# controller.net
KiCad netlist of a schematic drawn in EAGLE
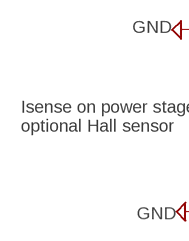
[diagram p0: schematic, sheet 1, part 1 of 2]
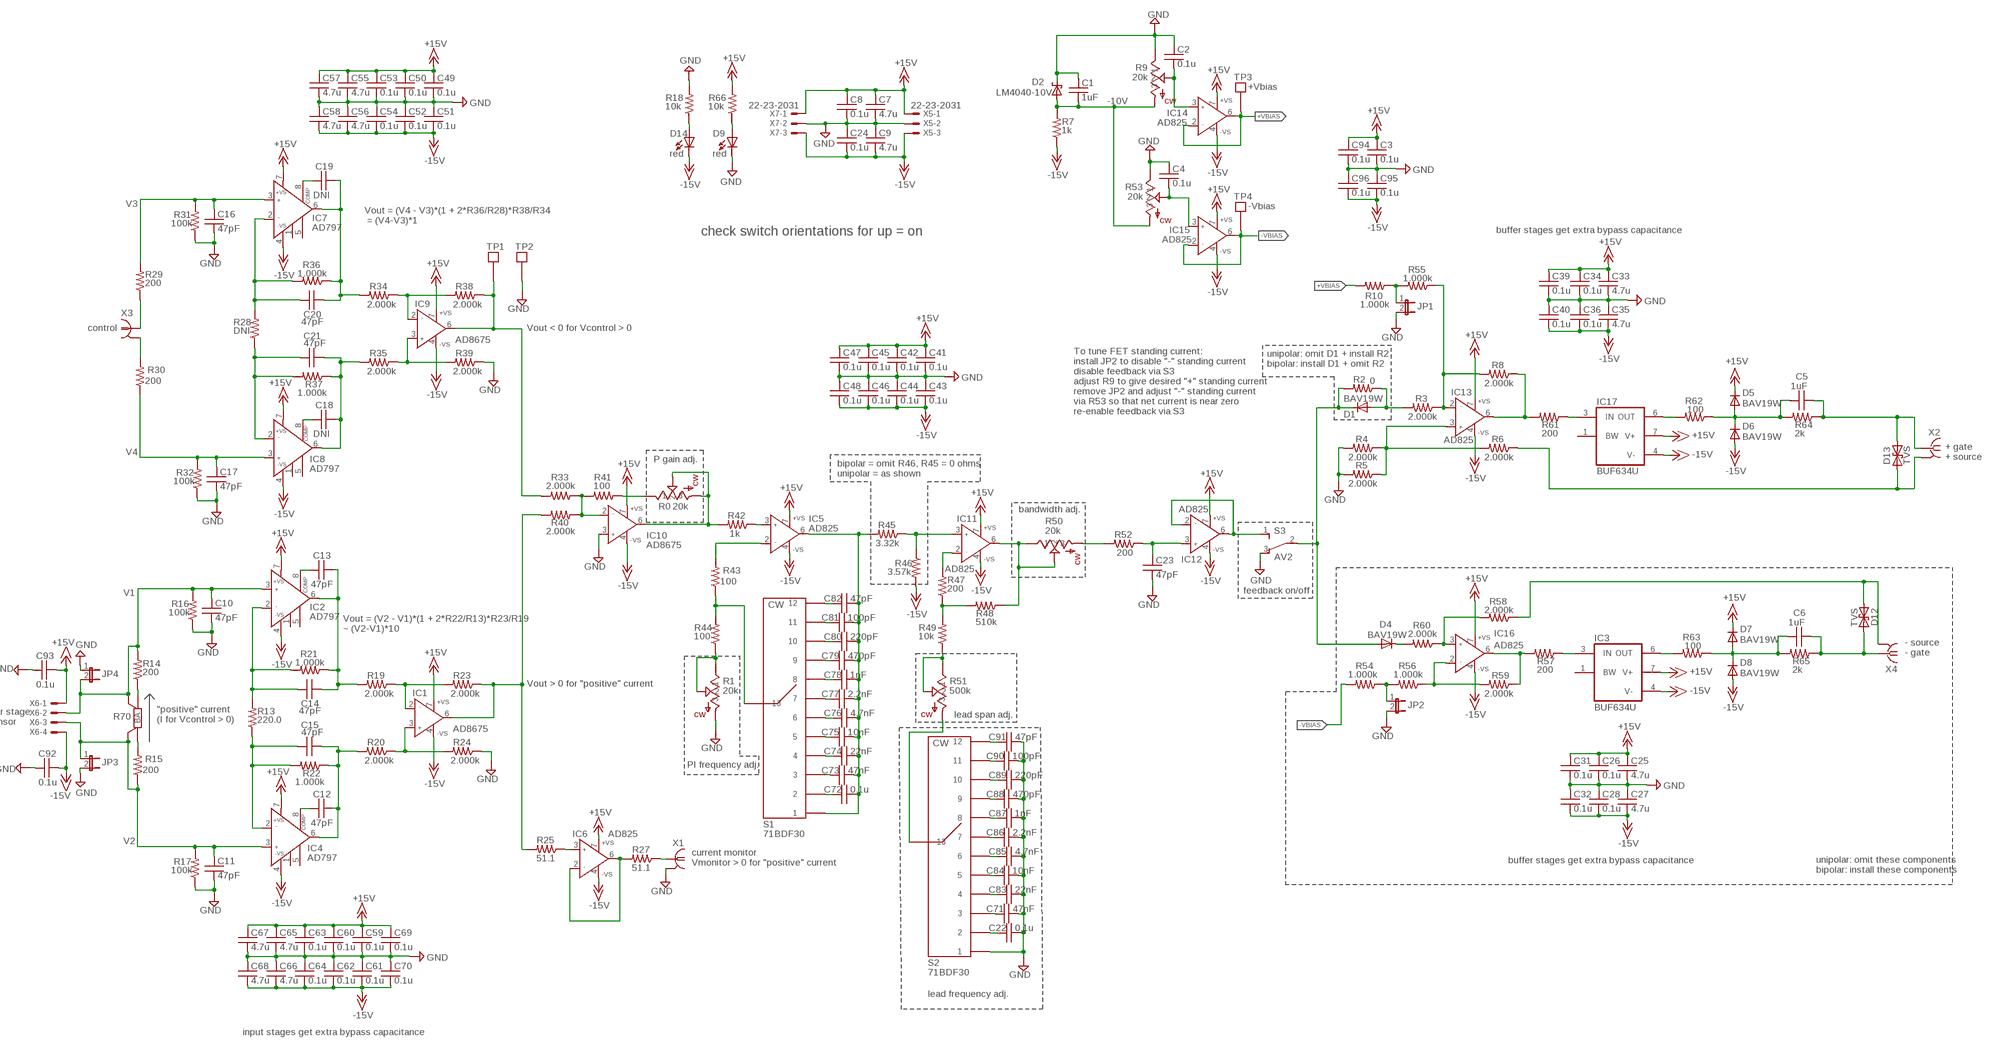
[diagram p1: schematic, sheet 1, part 2 of 2]

(export (version "E")
  (design (tool "Eeschema 10.0.6"))
  (components
    (comp (ref "C1")
      (value "1uF")
      (footprint "eagle-import:0603")
      (libsource (lib "eagle-import") (part "C0603"))
    )
    (comp (ref "C2")
      (value "0.1u")
      (footprint "eagle-import:0603")
      (libsource (lib "eagle-import") (part "C0603"))
    )
    (comp (ref "C3")
      (value "0.1u")
      (footprint "eagle-import:0603")
      (libsource (lib "eagle-import") (part "C0603"))
    )
    (comp (ref "C4")
      (value "0.1u")
      (footprint "eagle-import:0603")
      (libsource (lib "eagle-import") (part "C0603"))
    )
    (comp (ref "C5")
      (value "1uF")
      (footprint "eagle-import:0603")
      (libsource (lib "eagle-import") (part "C0603"))
    )
    (comp (ref "C6")
      (value "1uF")
      (footprint "eagle-import:0603")
      (libsource (lib "eagle-import") (part "C0603"))
    )
    (comp (ref "C7")
      (value "4.7u")
      (footprint "eagle-import:0603")
      (libsource (lib "eagle-import") (part "C0603"))
    )
    (comp (ref "C8")
      (value "0.1u")
      (footprint "eagle-import:0603")
      (libsource (lib "eagle-import") (part "C0603"))
    )
    (comp (ref "C9")
      (value "4.7u")
      (footprint "eagle-import:0603")
      (libsource (lib "eagle-import") (part "C0603"))
    )
    (comp (ref "C10")
      (value "47pF")
      (footprint "eagle-import:0603")
      (libsource (lib "eagle-import") (part "C0603"))
    )
    (comp (ref "C11")
      (value "47pF")
      (footprint "eagle-import:0603")
      (libsource (lib "eagle-import") (part "C0603"))
    )
    (comp (ref "C12")
      (value "47pF")
      (footprint "eagle-import:0603")
      (libsource (lib "eagle-import") (part "C0603"))
    )
    (comp (ref "C13")
      (value "47pF")
      (footprint "eagle-import:0603")
      (libsource (lib "eagle-import") (part "C0603"))
    )
    (comp (ref "C14")
      (value "47pF")
      (footprint "eagle-import:0603")
      (libsource (lib "eagle-import") (part "C0603"))
    )
    (comp (ref "C15")
      (value "47pF")
      (footprint "eagle-import:0603")
      (libsource (lib "eagle-import") (part "C0603"))
    )
    (comp (ref "C16")
      (value "47pF")
      (footprint "eagle-import:0603")
      (libsource (lib "eagle-import") (part "C0603"))
    )
    (comp (ref "C17")
      (value "47pF")
      (footprint "eagle-import:0603")
      (libsource (lib "eagle-import") (part "C0603"))
    )
    (comp (ref "C18")
      (value "DNI")
      (footprint "eagle-import:0603")
      (libsource (lib "eagle-import") (part "C0603"))
    )
    (comp (ref "C19")
      (value "DNI")
      (footprint "eagle-import:0603")
      (libsource (lib "eagle-import") (part "C0603"))
    )
    (comp (ref "C20")
      (value "47pF")
      (footprint "eagle-import:0603")
      (libsource (lib "eagle-import") (part "C0603"))
    )
    (comp (ref "C21")
      (value "47pF")
      (footprint "eagle-import:0603")
      (libsource (lib "eagle-import") (part "C0603"))
    )
    (comp (ref "C22")
      (value "0.1u")
      (footprint "eagle-import:0603")
      (libsource (lib "eagle-import") (part "C0603"))
    )
    (comp (ref "C23")
      (value "47pF")
      (footprint "eagle-import:0603")
      (libsource (lib "eagle-import") (part "C0603"))
    )
    (comp (ref "C24")
      (value "0.1u")
      (footprint "eagle-import:0603")
      (libsource (lib "eagle-import") (part "C0603"))
    )
    (comp (ref "C25")
      (value "4.7u")
      (footprint "eagle-import:0603")
      (libsource (lib "eagle-import") (part "C0603"))
    )
    (comp (ref "C26")
      (value "0.1u")
      (footprint "eagle-import:0603")
      (libsource (lib "eagle-import") (part "C0603"))
    )
    (comp (ref "C27")
      (value "4.7u")
      (footprint "eagle-import:0603")
      (libsource (lib "eagle-import") (part "C0603"))
    )
    (comp (ref "C28")
      (value "0.1u")
      (footprint "eagle-import:0603")
      (libsource (lib "eagle-import") (part "C0603"))
    )
    (comp (ref "C31")
      (value "0.1u")
      (footprint "eagle-import:0603")
      (libsource (lib "eagle-import") (part "C0603"))
    )
    (comp (ref "C32")
      (value "0.1u")
      (footprint "eagle-import:0603")
      (libsource (lib "eagle-import") (part "C0603"))
    )
    (comp (ref "C33")
      (value "4.7u")
      (footprint "eagle-import:0603")
      (libsource (lib "eagle-import") (part "C0603"))
    )
    (comp (ref "C34")
      (value "0.1u")
      (footprint "eagle-import:0603")
      (libsource (lib "eagle-import") (part "C0603"))
    )
    (comp (ref "C35")
      (value "4.7u")
      (footprint "eagle-import:0603")
      (libsource (lib "eagle-import") (part "C0603"))
    )
    (comp (ref "C36")
      (value "0.1u")
      (footprint "eagle-import:0603")
      (libsource (lib "eagle-import") (part "C0603"))
    )
    (comp (ref "C39")
      (value "0.1u")
      (footprint "eagle-import:0603")
      (libsource (lib "eagle-import") (part "C0603"))
    )
    (comp (ref "C40")
      (value "0.1u")
      (footprint "eagle-import:0603")
      (libsource (lib "eagle-import") (part "C0603"))
    )
    (comp (ref "C41")
      (value "0.1u")
      (footprint "eagle-import:0603")
      (libsource (lib "eagle-import") (part "C0603"))
    )
    (comp (ref "C42")
      (value "0.1u")
      (footprint "eagle-import:0603")
      (libsource (lib "eagle-import") (part "C0603"))
    )
    (comp (ref "C43")
      (value "0.1u")
      (footprint "eagle-import:0603")
      (libsource (lib "eagle-import") (part "C0603"))
    )
    (comp (ref "C44")
      (value "0.1u")
      (footprint "eagle-import:0603")
      (libsource (lib "eagle-import") (part "C0603"))
    )
    (comp (ref "C45")
      (value "0.1u")
      (footprint "eagle-import:0603")
      (libsource (lib "eagle-import") (part "C0603"))
    )
    (comp (ref "C46")
      (value "0.1u")
      (footprint "eagle-import:0603")
      (libsource (lib "eagle-import") (part "C0603"))
    )
    (comp (ref "C47")
      (value "0.1u")
      (footprint "eagle-import:0603")
      (libsource (lib "eagle-import") (part "C0603"))
    )
    (comp (ref "C48")
      (value "0.1u")
      (footprint "eagle-import:0603")
      (libsource (lib "eagle-import") (part "C0603"))
    )
    (comp (ref "C49")
      (value "0.1u")
      (footprint "eagle-import:0603")
      (libsource (lib "eagle-import") (part "C0603"))
    )
    (comp (ref "C50")
      (value "0.1u")
      (footprint "eagle-import:0603")
      (libsource (lib "eagle-import") (part "C0603"))
    )
    (comp (ref "C51")
      (value "0.1u")
      (footprint "eagle-import:0603")
      (libsource (lib "eagle-import") (part "C0603"))
    )
    (comp (ref "C52")
      (value "0.1u")
      (footprint "eagle-import:0603")
      (libsource (lib "eagle-import") (part "C0603"))
    )
    (comp (ref "C53")
      (value "0.1u")
      (footprint "eagle-import:0603")
      (libsource (lib "eagle-import") (part "C0603"))
    )
    (comp (ref "C54")
      (value "0.1u")
      (footprint "eagle-import:0603")
      (libsource (lib "eagle-import") (part "C0603"))
    )
    (comp (ref "C55")
      (value "4.7u")
      (footprint "eagle-import:0603")
      (libsource (lib "eagle-import") (part "C0603"))
    )
    (comp (ref "C56")
      (value "4.7u")
      (footprint "eagle-import:0603")
      (libsource (lib "eagle-import") (part "C0603"))
    )
    (comp (ref "C57")
      (value "4.7u")
      (footprint "eagle-import:0603")
      (libsource (lib "eagle-import") (part "C0603"))
    )
    (comp (ref "C58")
      (value "4.7u")
      (footprint "eagle-import:0603")
      (libsource (lib "eagle-import") (part "C0603"))
    )
    (comp (ref "C59")
      (value "0.1u")
      (footprint "eagle-import:0603")
      (libsource (lib "eagle-import") (part "C0603"))
    )
    (comp (ref "C60")
      (value "0.1u")
      (footprint "eagle-import:0603")
      (libsource (lib "eagle-import") (part "C0603"))
    )
    (comp (ref "C61")
      (value "0.1u")
      (footprint "eagle-import:0603")
      (libsource (lib "eagle-import") (part "C0603"))
    )
    (comp (ref "C62")
      (value "0.1u")
      (footprint "eagle-import:0603")
      (libsource (lib "eagle-import") (part "C0603"))
    )
    (comp (ref "C63")
      (value "0.1u")
      (footprint "eagle-import:0603")
      (libsource (lib "eagle-import") (part "C0603"))
    )
    (comp (ref "C64")
      (value "0.1u")
      (footprint "eagle-import:0603")
      (libsource (lib "eagle-import") (part "C0603"))
    )
    (comp (ref "C65")
      (value "4.7u")
      (footprint "eagle-import:0603")
      (libsource (lib "eagle-import") (part "C0603"))
    )
    (comp (ref "C66")
      (value "4.7u")
      (footprint "eagle-import:0603")
      (libsource (lib "eagle-import") (part "C0603"))
    )
    (comp (ref "C67")
      (value "4.7u")
      (footprint "eagle-import:0603")
      (libsource (lib "eagle-import") (part "C0603"))
    )
    (comp (ref "C68")
      (value "4.7u")
      (footprint "eagle-import:0603")
      (libsource (lib "eagle-import") (part "C0603"))
    )
    (comp (ref "C69")
      (value "0.1u")
      (footprint "eagle-import:0603")
      (libsource (lib "eagle-import") (part "C0603"))
    )
    (comp (ref "C70")
      (value "0.1u")
      (footprint "eagle-import:0603")
      (libsource (lib "eagle-import") (part "C0603"))
    )
    (comp (ref "C71")
      (value "47nF")
      (footprint "eagle-import:0603")
      (libsource (lib "eagle-import") (part "C0603"))
    )
    (comp (ref "C72")
      (value "0.1u")
      (footprint "eagle-import:0603")
      (libsource (lib "eagle-import") (part "C0603"))
    )
    (comp (ref "C73")
      (value "47nF")
      (footprint "eagle-import:0603")
      (libsource (lib "eagle-import") (part "C0603"))
    )
    (comp (ref "C74")
      (value "22nF")
      (footprint "eagle-import:0603")
      (libsource (lib "eagle-import") (part "C0603"))
    )
    (comp (ref "C75")
      (value "10nF")
      (footprint "eagle-import:0603")
      (libsource (lib "eagle-import") (part "C0603"))
    )
    (comp (ref "C76")
      (value "4.7nF")
      (footprint "eagle-import:0603")
      (libsource (lib "eagle-import") (part "C0603"))
    )
    (comp (ref "C77")
      (value "2.2nF")
      (footprint "eagle-import:0603")
      (libsource (lib "eagle-import") (part "C0603"))
    )
    (comp (ref "C78")
      (value "1nF")
      (footprint "eagle-import:0603")
      (libsource (lib "eagle-import") (part "C0603"))
    )
    (comp (ref "C79")
      (value "470pF")
      (footprint "eagle-import:0603")
      (libsource (lib "eagle-import") (part "C0603"))
    )
    (comp (ref "C80")
      (value "220pF")
      (footprint "eagle-import:0603")
      (libsource (lib "eagle-import") (part "C0603"))
    )
    (comp (ref "C81")
      (value "100pF")
      (footprint "eagle-import:0603")
      (libsource (lib "eagle-import") (part "C0603"))
    )
    (comp (ref "C82")
      (value "47pF")
      (footprint "eagle-import:0603")
      (libsource (lib "eagle-import") (part "C0603"))
    )
    (comp (ref "C83")
      (value "22nF")
      (footprint "eagle-import:0603")
      (libsource (lib "eagle-import") (part "C0603"))
    )
    (comp (ref "C84")
      (value "10nF")
      (footprint "eagle-import:0603")
      (libsource (lib "eagle-import") (part "C0603"))
    )
    (comp (ref "C85")
      (value "4.7nF")
      (footprint "eagle-import:0603")
      (libsource (lib "eagle-import") (part "C0603"))
    )
    (comp (ref "C86")
      (value "2.2nF")
      (footprint "eagle-import:0603")
      (libsource (lib "eagle-import") (part "C0603"))
    )
    (comp (ref "C87")
      (value "1nF")
      (footprint "eagle-import:0603")
      (libsource (lib "eagle-import") (part "C0603"))
    )
    (comp (ref "C88")
      (value "470pF")
      (footprint "eagle-import:0603")
      (libsource (lib "eagle-import") (part "C0603"))
    )
    (comp (ref "C89")
      (value "220pF")
      (footprint "eagle-import:0603")
      (libsource (lib "eagle-import") (part "C0603"))
    )
    (comp (ref "C90")
      (value "100pF")
      (footprint "eagle-import:0603")
      (libsource (lib "eagle-import") (part "C0603"))
    )
    (comp (ref "C91")
      (value "47pF")
      (footprint "eagle-import:0603")
      (libsource (lib "eagle-import") (part "C0603"))
    )
    (comp (ref "C92")
      (value "0.1u")
      (footprint "eagle-import:0603")
      (libsource (lib "eagle-import") (part "C0603"))
    )
    (comp (ref "C93")
      (value "0.1u")
      (footprint "eagle-import:0603")
      (libsource (lib "eagle-import") (part "C0603"))
    )
    (comp (ref "C94")
      (value "0.1u")
      (footprint "eagle-import:0603")
      (libsource (lib "eagle-import") (part "C0603"))
    )
    (comp (ref "C95")
      (value "0.1u")
      (footprint "eagle-import:0603")
      (libsource (lib "eagle-import") (part "C0603"))
    )
    (comp (ref "C96")
      (value "0.1u")
      (footprint "eagle-import:0603")
      (libsource (lib "eagle-import") (part "C0603"))
    )
    (comp (ref "D1")
      (value "BAV19W")
      (footprint "eagle-import:SOD123")
      (libsource (lib "eagle-import") (part "DIODE-SOD123"))
    )
    (comp (ref "D2")
      (value "LM4040-10V")
      (footprint "eagle-import:SOT23")
      (libsource (lib "eagle-import") (part "LM4040"))
    )
    (comp (ref "D4")
      (value "BAV19W")
      (footprint "eagle-import:SOD123")
      (libsource (lib "eagle-import") (part "DIODE-SOD123"))
    )
    (comp (ref "D5")
      (value "BAV19W")
      (footprint "eagle-import:SOD123")
      (libsource (lib "eagle-import") (part "DIODE-SOD123"))
    )
    (comp (ref "D6")
      (value "BAV19W")
      (footprint "eagle-import:SOD123")
      (libsource (lib "eagle-import") (part "DIODE-SOD123"))
    )
    (comp (ref "D7")
      (value "BAV19W")
      (footprint "eagle-import:SOD123")
      (libsource (lib "eagle-import") (part "DIODE-SOD123"))
    )
    (comp (ref "D8")
      (value "BAV19W")
      (footprint "eagle-import:SOD123")
      (libsource (lib "eagle-import") (part "DIODE-SOD123"))
    )
    (comp (ref "D9")
      (value "red")
      (footprint "eagle-import:LED0603")
      (libsource (lib "eagle-import") (part "LED0603"))
    )
    (comp (ref "D12")
      (value "TVS")
      (footprint "eagle-import:SMA-DIODE")
      (libsource (lib "eagle-import") (part "TVS"))
    )
    (comp (ref "D13")
      (value "TVS")
      (footprint "eagle-import:SMA-DIODE")
      (libsource (lib "eagle-import") (part "TVS"))
    )
    (comp (ref "D14")
      (value "red")
      (footprint "eagle-import:LED0603")
      (libsource (lib "eagle-import") (part "LED0603"))
    )
    (comp (ref "IC1")
      (value "AD8675")
      (footprint "eagle-import:SO8")
      (fields (field (name "MF") "ALTERA CORPORATION") (field (name "MPN") "AD825ARZ"))
      (libsource (lib "eagle-import") (part "AD825_BR"))
    )
    (comp (ref "IC2")
      (value "AD797")
      (footprint "eagle-import:SO8")
      (fields (field (name "MF") "ALTERA CORPORATION") (field (name "MPN") "AD797ARZ"))
      (libsource (lib "eagle-import") (part "AD797_AR"))
    )
    (comp (ref "IC3")
      (value "BUF634U")
      (footprint "eagle-import:SO08")
      (fields (field (name "MF") "TEXAS INSTRUMENTS"))
      (libsource (lib "eagle-import") (part "BUF634U"))
    )
    (comp (ref "IC4")
      (value "AD797")
      (footprint "eagle-import:SO8")
      (fields (field (name "MF") "ALTERA CORPORATION") (field (name "MPN") "AD797ARZ"))
      (libsource (lib "eagle-import") (part "AD797_BR"))
    )
    (comp (ref "IC5")
      (value "AD825")
      (footprint "eagle-import:SO08")
      (libsource (lib "eagle-import") (part "AD825_A"))
    )
    (comp (ref "IC6")
      (value "AD825")
      (footprint "eagle-import:SO08")
      (libsource (lib "eagle-import") (part "AD825_A"))
    )
    (comp (ref "IC7")
      (value "AD797")
      (footprint "eagle-import:SO8")
      (fields (field (name "MF") "ALTERA CORPORATION") (field (name "MPN") "AD797ARZ"))
      (libsource (lib "eagle-import") (part "AD797_AR"))
    )
    (comp (ref "IC8")
      (value "AD797")
      (footprint "eagle-import:SO8")
      (fields (field (name "MF") "ALTERA CORPORATION") (field (name "MPN") "AD797ARZ"))
      (libsource (lib "eagle-import") (part "AD797_BR"))
    )
    (comp (ref "IC9")
      (value "AD8675")
      (footprint "eagle-import:SO8")
      (fields (field (name "MF") "ALTERA CORPORATION") (field (name "MPN") "AD825ARZ"))
      (libsource (lib "eagle-import") (part "AD825_BR"))
    )
    (comp (ref "IC10")
      (value "AD8675")
      (footprint "eagle-import:SO8")
      (fields (field (name "MF") "ALTERA CORPORATION") (field (name "MPN") "AD825ARZ"))
      (libsource (lib "eagle-import") (part "AD825_BR"))
    )
    (comp (ref "IC11")
      (value "AD825")
      (footprint "eagle-import:SO08")
      (libsource (lib "eagle-import") (part "AD825_A"))
    )
    (comp (ref "IC12")
      (value "AD825")
      (footprint "eagle-import:SO8")
      (fields (field (name "MF") "ALTERA CORPORATION") (field (name "MPN") "AD825ARZ"))
      (libsource (lib "eagle-import") (part "AD825_BR"))
    )
    (comp (ref "IC13")
      (value "AD825")
      (footprint "eagle-import:SO8")
      (fields (field (name "MF") "ALTERA CORPORATION") (field (name "MPN") "AD825ARZ"))
      (libsource (lib "eagle-import") (part "AD825_BR"))
    )
    (comp (ref "IC14")
      (value "AD825")
      (footprint "eagle-import:SO08")
      (libsource (lib "eagle-import") (part "AD825_A"))
    )
    (comp (ref "IC15")
      (value "AD825")
      (footprint "eagle-import:SO08")
      (libsource (lib "eagle-import") (part "AD825_A"))
    )
    (comp (ref "IC16")
      (value "AD825")
      (footprint "eagle-import:SO08")
      (libsource (lib "eagle-import") (part "AD825_A"))
    )
    (comp (ref "IC17")
      (value "BUF634U")
      (footprint "eagle-import:SO08")
      (fields (field (name "MF") "TEXAS INSTRUMENTS"))
      (libsource (lib "eagle-import") (part "BUF634U"))
    )
    (comp (ref "JP1")
      (value "JP1E")
      (footprint "eagle-import:JP1")
      (libsource (lib "eagle-import") (part "JP1E"))
    )
    (comp (ref "JP2")
      (value "JP1E")
      (footprint "eagle-import:JP1")
      (libsource (lib "eagle-import") (part "JP1E"))
    )
    (comp (ref "JP3")
      (value "JP1E")
      (footprint "eagle-import:JP1")
      (libsource (lib "eagle-import") (part "JP1E"))
    )
    (comp (ref "JP4")
      (value "JP1E")
      (footprint "eagle-import:JP1")
      (libsource (lib "eagle-import") (part "JP1E"))
    )
    (comp (ref "R0")
      (value "20k")
      (footprint "eagle-import:3590")
      (libsource (lib "eagle-import") (part "POT"))
    )
    (comp (ref "R1")
      (value "20k")
      (footprint "eagle-import:SP19L")
      (libsource (lib "eagle-import") (part "TRIM_US-B90P"))
    )
    (comp (ref "R2")
      (value "0")
      (footprint "eagle-import:0603")
      (libsource (lib "eagle-import") (part "R0603"))
    )
    (comp (ref "R3")
      (value "2.000k")
      (footprint "eagle-import:0603")
      (libsource (lib "eagle-import") (part "R0603"))
    )
    (comp (ref "R4")
      (value "2.000k")
      (footprint "eagle-import:0603")
      (libsource (lib "eagle-import") (part "R0603"))
    )
    (comp (ref "R5")
      (value "2.000k")
      (footprint "eagle-import:0603")
      (libsource (lib "eagle-import") (part "R0603"))
    )
    (comp (ref "R6")
      (value "2.000k")
      (footprint "eagle-import:0603")
      (libsource (lib "eagle-import") (part "R0603"))
    )
    (comp (ref "R7")
      (value "1k")
      (footprint "eagle-import:0603")
      (libsource (lib "eagle-import") (part "R0603"))
    )
    (comp (ref "R8")
      (value "2.000k")
      (footprint "eagle-import:0603")
      (libsource (lib "eagle-import") (part "R0603"))
    )
    (comp (ref "R9")
      (value "20k")
      (footprint "eagle-import:SP19L")
      (libsource (lib "eagle-import") (part "TRIM_US-B90P"))
    )
    (comp (ref "R10")
      (value "1.000k")
      (footprint "eagle-import:0603")
      (libsource (lib "eagle-import") (part "R0603"))
    )
    (comp (ref "R13")
      (value "220.0")
      (footprint "eagle-import:0603")
      (libsource (lib "eagle-import") (part "R0603"))
    )
    (comp (ref "R14")
      (value "200")
      (footprint "eagle-import:0603")
      (libsource (lib "eagle-import") (part "R0603"))
    )
    (comp (ref "R15")
      (value "200")
      (footprint "eagle-import:0603")
      (libsource (lib "eagle-import") (part "R0603"))
    )
    (comp (ref "R16")
      (value "100k")
      (footprint "eagle-import:0603")
      (libsource (lib "eagle-import") (part "R0603"))
    )
    (comp (ref "R17")
      (value "100k")
      (footprint "eagle-import:0603")
      (libsource (lib "eagle-import") (part "R0603"))
    )
    (comp (ref "R18")
      (value "10k")
      (footprint "eagle-import:0603")
      (libsource (lib "eagle-import") (part "R0603"))
    )
    (comp (ref "R19")
      (value "2.000k")
      (footprint "eagle-import:0603")
      (libsource (lib "eagle-import") (part "R0603"))
    )
    (comp (ref "R20")
      (value "2.000k")
      (footprint "eagle-import:0603")
      (libsource (lib "eagle-import") (part "R0603"))
    )
    (comp (ref "R21")
      (value "1.000k")
      (footprint "eagle-import:0603")
      (libsource (lib "eagle-import") (part "R0603"))
    )
    (comp (ref "R22")
      (value "1.000k")
      (footprint "eagle-import:0603")
      (libsource (lib "eagle-import") (part "R0603"))
    )
    (comp (ref "R23")
      (value "2.000k")
      (footprint "eagle-import:0603")
      (libsource (lib "eagle-import") (part "R0603"))
    )
    (comp (ref "R24")
      (value "2.000k")
      (footprint "eagle-import:0603")
      (libsource (lib "eagle-import") (part "R0603"))
    )
    (comp (ref "R25")
      (value "51.1")
      (footprint "eagle-import:0603")
      (libsource (lib "eagle-import") (part "R0603"))
    )
    (comp (ref "R27")
      (value "51.1")
      (footprint "eagle-import:0603")
      (libsource (lib "eagle-import") (part "R0603"))
    )
    (comp (ref "R28")
      (value "DNI")
      (footprint "eagle-import:0603")
      (libsource (lib "eagle-import") (part "R0603"))
    )
    (comp (ref "R29")
      (value "200")
      (footprint "eagle-import:0603")
      (libsource (lib "eagle-import") (part "R0603"))
    )
    (comp (ref "R30")
      (value "200")
      (footprint "eagle-import:0603")
      (libsource (lib "eagle-import") (part "R0603"))
    )
    (comp (ref "R31")
      (value "100k")
      (footprint "eagle-import:0603")
      (libsource (lib "eagle-import") (part "R0603"))
    )
    (comp (ref "R32")
      (value "100k")
      (footprint "eagle-import:0603")
      (libsource (lib "eagle-import") (part "R0603"))
    )
    (comp (ref "R33")
      (value "2.000k")
      (footprint "eagle-import:0603")
      (libsource (lib "eagle-import") (part "R0603"))
    )
    (comp (ref "R34")
      (value "2.000k")
      (footprint "eagle-import:0603")
      (libsource (lib "eagle-import") (part "R0603"))
    )
    (comp (ref "R35")
      (value "2.000k")
      (footprint "eagle-import:0603")
      (libsource (lib "eagle-import") (part "R0603"))
    )
    (comp (ref "R36")
      (value "1.000k")
      (footprint "eagle-import:0603")
      (libsource (lib "eagle-import") (part "R0603"))
    )
    (comp (ref "R37")
      (value "1.000k")
      (footprint "eagle-import:0603")
      (libsource (lib "eagle-import") (part "R0603"))
    )
    (comp (ref "R38")
      (value "2.000k")
      (footprint "eagle-import:0603")
      (libsource (lib "eagle-import") (part "R0603"))
    )
    (comp (ref "R39")
      (value "2.000k")
      (footprint "eagle-import:0603")
      (libsource (lib "eagle-import") (part "R0603"))
    )
    (comp (ref "R40")
      (value "2.000k")
      (footprint "eagle-import:0603")
      (libsource (lib "eagle-import") (part "R0603"))
    )
    (comp (ref "R41")
      (value "100")
      (footprint "eagle-import:0603")
      (libsource (lib "eagle-import") (part "R0603"))
    )
    (comp (ref "R42")
      (value "1k")
      (footprint "eagle-import:0603")
      (libsource (lib "eagle-import") (part "R0603"))
    )
    (comp (ref "R43")
      (value "100")
      (footprint "eagle-import:0603")
      (libsource (lib "eagle-import") (part "R0603"))
    )
    (comp (ref "R44")
      (value "100")
      (footprint "eagle-import:0603")
      (libsource (lib "eagle-import") (part "R0603"))
    )
    (comp (ref "R45")
      (value "3.32k")
      (footprint "eagle-import:0603")
      (libsource (lib "eagle-import") (part "R0603"))
    )
    (comp (ref "R46")
      (value "3.57k")
      (footprint "eagle-import:0603")
      (libsource (lib "eagle-import") (part "R0603"))
    )
    (comp (ref "R47")
      (value "200")
      (footprint "eagle-import:0603")
      (libsource (lib "eagle-import") (part "R0603"))
    )
    (comp (ref "R48")
      (value "510k")
      (footprint "eagle-import:0603")
      (libsource (lib "eagle-import") (part "R0603"))
    )
    (comp (ref "R49")
      (value "10k")
      (footprint "eagle-import:0603")
      (libsource (lib "eagle-import") (part "R0603"))
    )
    (comp (ref "R50")
      (value "20k")
      (footprint "eagle-import:SP19L")
      (libsource (lib "eagle-import") (part "TRIM_US-B90P"))
    )
    (comp (ref "R51")
      (value "500k")
      (footprint "eagle-import:SP19L")
      (libsource (lib "eagle-import") (part "TRIM_US-B90P"))
    )
    (comp (ref "R52")
      (value "200")
      (footprint "eagle-import:0603")
      (libsource (lib "eagle-import") (part "R0603"))
    )
    (comp (ref "R53")
      (value "20k")
      (footprint "eagle-import:SP19L")
      (libsource (lib "eagle-import") (part "TRIM_US-B90P"))
    )
    (comp (ref "R54")
      (value "1.000k")
      (footprint "eagle-import:0603")
      (libsource (lib "eagle-import") (part "R0603"))
    )
    (comp (ref "R55")
      (value "1.000k")
      (footprint "eagle-import:0603")
      (libsource (lib "eagle-import") (part "R0603"))
    )
    (comp (ref "R56")
      (value "1.000k")
      (footprint "eagle-import:0603")
      (libsource (lib "eagle-import") (part "R0603"))
    )
    (comp (ref "R57")
      (value "200")
      (footprint "eagle-import:0603")
      (libsource (lib "eagle-import") (part "R0603"))
    )
    (comp (ref "R58")
      (value "2.000k")
      (footprint "eagle-import:0603")
      (libsource (lib "eagle-import") (part "R0603"))
    )
    (comp (ref "R59")
      (value "2.000k")
      (footprint "eagle-import:0603")
      (libsource (lib "eagle-import") (part "R0603"))
    )
    (comp (ref "R60")
      (value "2.000k")
      (footprint "eagle-import:0603")
      (libsource (lib "eagle-import") (part "R0603"))
    )
    (comp (ref "R61")
      (value "200")
      (footprint "eagle-import:0603")
      (libsource (lib "eagle-import") (part "R0603"))
    )
    (comp (ref "R62")
      (value "100")
      (footprint "eagle-import:0603")
      (libsource (lib "eagle-import") (part "R0603"))
    )
    (comp (ref "R63")
      (value "100")
      (footprint "eagle-import:0603")
      (libsource (lib "eagle-import") (part "R0603"))
    )
    (comp (ref "R64")
      (value "2k")
      (footprint "eagle-import:0603")
      (libsource (lib "eagle-import") (part "R0603"))
    )
    (comp (ref "R65")
      (value "2k")
      (footprint "eagle-import:0603")
      (libsource (lib "eagle-import") (part "R0603"))
    )
    (comp (ref "R66")
      (value "10k")
      (footprint "eagle-import:0603")
      (libsource (lib "eagle-import") (part "R0603"))
    )
    (comp (ref "R70")
      (value "RSENSE")
      (footprint "eagle-import:22-23-2041")
      (libsource (lib "eagle-import") (part "RSENSE"))
    )
    (comp (ref "S1")
      (value "71BDF30")
      (footprint "eagle-import:71BDF")
      (libsource (lib "eagle-import") (part "71BDF30"))
    )
    (comp (ref "S2")
      (value "71BDF30")
      (footprint "eagle-import:71BDF")
      (libsource (lib "eagle-import") (part "71BDF30"))
    )
    (comp (ref "S3")
      (value "AV2")
      (footprint "eagle-import:SPDT-AV2")
      (libsource (lib "eagle-import") (part "SPDT"))
    )
    (comp (ref "TP1")
      (value "TESTPOINT")
      (footprint "eagle-import:TESTPOINT")
      (libsource (lib "eagle-import") (part "TESTPOINT"))
    )
    (comp (ref "TP2")
      (value "TESTPOINT")
      (footprint "eagle-import:TESTPOINT")
      (libsource (lib "eagle-import") (part "TESTPOINT"))
    )
    (comp (ref "TP3")
      (value "TESTPOINT")
      (footprint "eagle-import:TESTPOINT")
      (libsource (lib "eagle-import") (part "TESTPOINT"))
    )
    (comp (ref "TP4")
      (value "TESTPOINT")
      (footprint "eagle-import:TESTPOINT")
      (libsource (lib "eagle-import") (part "TESTPOINT"))
    )
    (comp (ref "X1")
      (value "1-227161-0")
      (footprint "eagle-import:AMP_227161")
      (fields (field (name "MF") "TYCO ELECTRONICS") (field (name "MPN") "1-227161"))
      (libsource (lib "eagle-import") (part "?2271611--0"))
    )
    (comp (ref "X2")
      (value "BU-SMA-H")
      (footprint "eagle-import:BU-SMA-H")
      (libsource (lib "eagle-import") (part "BU-SMA-H"))
    )
    (comp (ref "X3")
      (value "1-227161-0")
      (footprint "eagle-import:AMP_227161")
      (fields (field (name "MF") "TYCO ELECTRONICS") (field (name "MPN") "1-227161"))
      (libsource (lib "eagle-import") (part "?2271611--0"))
    )
    (comp (ref "X4")
      (value "BU-SMA-H")
      (footprint "eagle-import:BU-SMA-H")
      (libsource (lib "eagle-import") (part "BU-SMA-H"))
    )
    (comp (ref "X5")
      (value "22-23-2031")
      (footprint "eagle-import:22-23-2031")
      (fields (field (name "MF") "MOLEX"))
      (libsource (lib "eagle-import") (part "22-23-2031"))
    )
    (comp (ref "X6")
      (value "22-23-2041")
      (footprint "eagle-import:22-23-2041")
      (fields (field (name "MF") "MOLEX"))
      (libsource (lib "eagle-import") (part "22-23-2041"))
    )
    (comp (ref "X7")
      (value "22-23-2031")
      (footprint "eagle-import:22-23-2031")
      (fields (field (name "MF") "MOLEX"))
      (libsource (lib "eagle-import") (part "22-23-2031"))
    )
  )
  (nets
    (net (code "1") (name "+15V") (class "Default")
      (node (ref "C25") (pin "1") (pinfunction "1_1") (pintype "passive"))
      (node (ref "C26") (pin "1") (pinfunction "1_1") (pintype "passive"))
      (node (ref "C3") (pin "1") (pinfunction "1_1") (pintype "passive"))
      (node (ref "C31") (pin "1") (pinfunction "1_1") (pintype "passive"))
      (node (ref "C33") (pin "1") (pinfunction "1_1") (pintype "passive"))
      (node (ref "C34") (pin "1") (pinfunction "1_1") (pintype "passive"))
      (node (ref "C39") (pin "1") (pinfunction "1_1") (pintype "passive"))
      (node (ref "C41") (pin "1") (pinfunction "1_1") (pintype "passive"))
      (node (ref "C42") (pin "1") (pinfunction "1_1") (pintype "passive"))
      (node (ref "C45") (pin "1") (pinfunction "1_1") (pintype "passive"))
      (node (ref "C47") (pin "1") (pinfunction "1_1") (pintype "passive"))
      (node (ref "C49") (pin "1") (pinfunction "1_1") (pintype "passive"))
      (node (ref "C50") (pin "1") (pinfunction "1_1") (pintype "passive"))
      (node (ref "C53") (pin "1") (pinfunction "1_1") (pintype "passive"))
      (node (ref "C55") (pin "1") (pinfunction "1_1") (pintype "passive"))
      (node (ref "C57") (pin "1") (pinfunction "1_1") (pintype "passive"))
      (node (ref "C59") (pin "1") (pinfunction "1_1") (pintype "passive"))
      (node (ref "C60") (pin "1") (pinfunction "1_1") (pintype "passive"))
      (node (ref "C63") (pin "1") (pinfunction "1_1") (pintype "passive"))
      (node (ref "C65") (pin "1") (pinfunction "1_1") (pintype "passive"))
      (node (ref "C67") (pin "1") (pinfunction "1_1") (pintype "passive"))
      (node (ref "C69") (pin "1") (pinfunction "1_1") (pintype "passive"))
      (node (ref "C7") (pin "1") (pinfunction "1_1") (pintype "passive"))
      (node (ref "C8") (pin "1") (pinfunction "1_1") (pintype "passive"))
      (node (ref "C93") (pin "2") (pinfunction "2_2") (pintype "passive"))
      (node (ref "C94") (pin "1") (pinfunction "1_1") (pintype "passive"))
      (node (ref "D5") (pin "C") (pinfunction "C_C") (pintype "passive"))
      (node (ref "D7") (pin "C") (pinfunction "C_C") (pintype "passive"))
      (node (ref "IC1") (pin "7") (pinfunction "+VS_7") (pintype "input"))
      (node (ref "IC10") (pin "7") (pinfunction "+VS_7") (pintype "input"))
      (node (ref "IC11") (pin "7") (pinfunction "+VS_7") (pintype "input"))
      (node (ref "IC12") (pin "7") (pinfunction "+VS_7") (pintype "input"))
      (node (ref "IC13") (pin "7") (pinfunction "+VS_7") (pintype "input"))
      (node (ref "IC14") (pin "7") (pinfunction "+VS_7") (pintype "input"))
      (node (ref "IC15") (pin "7") (pinfunction "+VS_7") (pintype "input"))
      (node (ref "IC16") (pin "7") (pinfunction "+VS_7") (pintype "input"))
      (node (ref "IC17") (pin "7") (pinfunction "V+_7") (pintype "power_in"))
      (node (ref "IC2") (pin "7") (pinfunction "+VS_7") (pintype "input"))
      (node (ref "IC3") (pin "7") (pinfunction "V+_7") (pintype "power_in"))
      (node (ref "IC4") (pin "7") (pinfunction "+VS_7") (pintype "input"))
      (node (ref "IC5") (pin "7") (pinfunction "+VS_7") (pintype "input"))
      (node (ref "IC6") (pin "7") (pinfunction "+VS_7") (pintype "input"))
      (node (ref "IC7") (pin "7") (pinfunction "+VS_7") (pintype "input"))
      (node (ref "IC8") (pin "7") (pinfunction "+VS_7") (pintype "input"))
      (node (ref "IC9") (pin "7") (pinfunction "+VS_7") (pintype "input"))
      (node (ref "R66") (pin "2") (pinfunction "2_2") (pintype "passive"))
      (node (ref "X5") (pin "1") (pinfunction "S_1") (pintype "passive"))
      (node (ref "X6") (pin "1") (pinfunction "S_1") (pintype "passive"))
      (node (ref "X7") (pin "1") (pinfunction "S_1") (pintype "passive"))
    )
    (net (code "2") (name "+VBIAS") (class "Default")
      (node (ref "IC14") (pin "2") (pinfunction "IN-_2") (pintype "input"))
      (node (ref "IC14") (pin "6") (pinfunction "OUT_6") (pintype "output"))
      (node (ref "R10") (pin "2") (pinfunction "2_2") (pintype "passive"))
      (node (ref "TP3") (pin "P$1") (pinfunction "P$1_P$1") (pintype "bidirectional"))
    )
    (net (code "3") (name "-15V") (class "Default")
      (node (ref "C24") (pin "2") (pinfunction "2_2") (pintype "passive"))
      (node (ref "C27") (pin "2") (pinfunction "2_2") (pintype "passive"))
      (node (ref "C28") (pin "2") (pinfunction "2_2") (pintype "passive"))
      (node (ref "C32") (pin "2") (pinfunction "2_2") (pintype "passive"))
      (node (ref "C35") (pin "2") (pinfunction "2_2") (pintype "passive"))
      (node (ref "C36") (pin "2") (pinfunction "2_2") (pintype "passive"))
      (node (ref "C40") (pin "2") (pinfunction "2_2") (pintype "passive"))
      (node (ref "C43") (pin "2") (pinfunction "2_2") (pintype "passive"))
      (node (ref "C44") (pin "2") (pinfunction "2_2") (pintype "passive"))
      (node (ref "C46") (pin "2") (pinfunction "2_2") (pintype "passive"))
      (node (ref "C48") (pin "2") (pinfunction "2_2") (pintype "passive"))
      (node (ref "C51") (pin "2") (pinfunction "2_2") (pintype "passive"))
      (node (ref "C52") (pin "2") (pinfunction "2_2") (pintype "passive"))
      (node (ref "C54") (pin "2") (pinfunction "2_2") (pintype "passive"))
      (node (ref "C56") (pin "2") (pinfunction "2_2") (pintype "passive"))
      (node (ref "C58") (pin "2") (pinfunction "2_2") (pintype "passive"))
      (node (ref "C61") (pin "2") (pinfunction "2_2") (pintype "passive"))
      (node (ref "C62") (pin "2") (pinfunction "2_2") (pintype "passive"))
      (node (ref "C64") (pin "2") (pinfunction "2_2") (pintype "passive"))
      (node (ref "C66") (pin "2") (pinfunction "2_2") (pintype "passive"))
      (node (ref "C68") (pin "2") (pinfunction "2_2") (pintype "passive"))
      (node (ref "C70") (pin "2") (pinfunction "2_2") (pintype "passive"))
      (node (ref "C9") (pin "2") (pinfunction "2_2") (pintype "passive"))
      (node (ref "C92") (pin "2") (pinfunction "2_2") (pintype "passive"))
      (node (ref "C95") (pin "2") (pinfunction "2_2") (pintype "passive"))
      (node (ref "C96") (pin "2") (pinfunction "2_2") (pintype "passive"))
      (node (ref "D14") (pin "C") (pinfunction "C_C") (pintype "passive"))
      (node (ref "D6") (pin "A") (pinfunction "A_A") (pintype "passive"))
      (node (ref "D8") (pin "A") (pinfunction "A_A") (pintype "passive"))
      (node (ref "IC1") (pin "4") (pinfunction "-VS_4") (pintype "input"))
      (node (ref "IC10") (pin "4") (pinfunction "-VS_4") (pintype "input"))
      (node (ref "IC11") (pin "4") (pinfunction "-VS_4") (pintype "input"))
      (node (ref "IC12") (pin "4") (pinfunction "-VS_4") (pintype "input"))
      (node (ref "IC13") (pin "4") (pinfunction "-VS_4") (pintype "input"))
      (node (ref "IC14") (pin "4") (pinfunction "-VS_4") (pintype "input"))
      (node (ref "IC15") (pin "4") (pinfunction "-VS_4") (pintype "input"))
      (node (ref "IC16") (pin "4") (pinfunction "-VS_4") (pintype "input"))
      (node (ref "IC17") (pin "4") (pinfunction "V-_4") (pintype "power_in"))
      (node (ref "IC2") (pin "4") (pinfunction "-VS_4") (pintype "input"))
      (node (ref "IC3") (pin "4") (pinfunction "V-_4") (pintype "power_in"))
      (node (ref "IC4") (pin "4") (pinfunction "-VS_4") (pintype "input"))
      (node (ref "IC5") (pin "4") (pinfunction "-VS_4") (pintype "input"))
      (node (ref "IC6") (pin "4") (pinfunction "-VS_4") (pintype "input"))
      (node (ref "IC7") (pin "4") (pinfunction "-VS_4") (pintype "input"))
      (node (ref "IC8") (pin "4") (pinfunction "-VS_4") (pintype "input"))
      (node (ref "IC9") (pin "4") (pinfunction "-VS_4") (pintype "input"))
      (node (ref "R46") (pin "2") (pinfunction "2_2") (pintype "passive"))
      (node (ref "R7") (pin "1") (pinfunction "1_1") (pintype "passive"))
      (node (ref "X5") (pin "3") (pinfunction "S_3") (pintype "passive"))
      (node (ref "X6") (pin "4") (pinfunction "S_4") (pintype "passive"))
      (node (ref "X7") (pin "3") (pinfunction "S_3") (pintype "passive"))
    )
    (net (code "4") (name "-VBIAS") (class "Default")
      (node (ref "IC15") (pin "2") (pinfunction "IN-_2") (pintype "input"))
      (node (ref "IC15") (pin "6") (pinfunction "OUT_6") (pintype "output"))
      (node (ref "R54") (pin "2") (pinfunction "2_2") (pintype "passive"))
      (node (ref "TP4") (pin "P$1") (pinfunction "P$1_P$1") (pintype "bidirectional"))
    )
    (net (code "5") (name "GND") (class "Default")
      (node (ref "C1") (pin "1") (pinfunction "1_1") (pintype "passive"))
      (node (ref "C10") (pin "2") (pinfunction "2_2") (pintype "passive"))
      (node (ref "C11") (pin "2") (pinfunction "2_2") (pintype "passive"))
      (node (ref "C16") (pin "2") (pinfunction "2_2") (pintype "passive"))
      (node (ref "C17") (pin "2") (pinfunction "2_2") (pintype "passive"))
      (node (ref "C2") (pin "1") (pinfunction "1_1") (pintype "passive"))
      (node (ref "C22") (pin "2") (pinfunction "2_2") (pintype "passive"))
      (node (ref "C23") (pin "2") (pinfunction "2_2") (pintype "passive"))
      (node (ref "C24") (pin "1") (pinfunction "1_1") (pintype "passive"))
      (node (ref "C25") (pin "2") (pinfunction "2_2") (pintype "passive"))
      (node (ref "C26") (pin "2") (pinfunction "2_2") (pintype "passive"))
      (node (ref "C27") (pin "1") (pinfunction "1_1") (pintype "passive"))
      (node (ref "C28") (pin "1") (pinfunction "1_1") (pintype "passive"))
      (node (ref "C3") (pin "2") (pinfunction "2_2") (pintype "passive"))
      (node (ref "C31") (pin "2") (pinfunction "2_2") (pintype "passive"))
      (node (ref "C32") (pin "1") (pinfunction "1_1") (pintype "passive"))
      (node (ref "C33") (pin "2") (pinfunction "2_2") (pintype "passive"))
      (node (ref "C34") (pin "2") (pinfunction "2_2") (pintype "passive"))
      (node (ref "C35") (pin "1") (pinfunction "1_1") (pintype "passive"))
      (node (ref "C36") (pin "1") (pinfunction "1_1") (pintype "passive"))
      (node (ref "C39") (pin "2") (pinfunction "2_2") (pintype "passive"))
      (node (ref "C4") (pin "1") (pinfunction "1_1") (pintype "passive"))
      (node (ref "C40") (pin "1") (pinfunction "1_1") (pintype "passive"))
      (node (ref "C41") (pin "2") (pinfunction "2_2") (pintype "passive"))
      (node (ref "C42") (pin "2") (pinfunction "2_2") (pintype "passive"))
      (node (ref "C43") (pin "1") (pinfunction "1_1") (pintype "passive"))
      (node (ref "C44") (pin "1") (pinfunction "1_1") (pintype "passive"))
      (node (ref "C45") (pin "2") (pinfunction "2_2") (pintype "passive"))
      (node (ref "C46") (pin "1") (pinfunction "1_1") (pintype "passive"))
      (node (ref "C47") (pin "2") (pinfunction "2_2") (pintype "passive"))
      (node (ref "C48") (pin "1") (pinfunction "1_1") (pintype "passive"))
      (node (ref "C49") (pin "2") (pinfunction "2_2") (pintype "passive"))
      (node (ref "C50") (pin "2") (pinfunction "2_2") (pintype "passive"))
      (node (ref "C51") (pin "1") (pinfunction "1_1") (pintype "passive"))
      (node (ref "C52") (pin "1") (pinfunction "1_1") (pintype "passive"))
      (node (ref "C53") (pin "2") (pinfunction "2_2") (pintype "passive"))
      (node (ref "C54") (pin "1") (pinfunction "1_1") (pintype "passive"))
      (node (ref "C55") (pin "2") (pinfunction "2_2") (pintype "passive"))
      (node (ref "C56") (pin "1") (pinfunction "1_1") (pintype "passive"))
      (node (ref "C57") (pin "2") (pinfunction "2_2") (pintype "passive"))
      (node (ref "C58") (pin "1") (pinfunction "1_1") (pintype "passive"))
      (node (ref "C59") (pin "2") (pinfunction "2_2") (pintype "passive"))
      (node (ref "C60") (pin "2") (pinfunction "2_2") (pintype "passive"))
      (node (ref "C61") (pin "1") (pinfunction "1_1") (pintype "passive"))
      (node (ref "C62") (pin "1") (pinfunction "1_1") (pintype "passive"))
      (node (ref "C63") (pin "2") (pinfunction "2_2") (pintype "passive"))
      (node (ref "C64") (pin "1") (pinfunction "1_1") (pintype "passive"))
      (node (ref "C65") (pin "2") (pinfunction "2_2") (pintype "passive"))
      (node (ref "C66") (pin "1") (pinfunction "1_1") (pintype "passive"))
      (node (ref "C67") (pin "2") (pinfunction "2_2") (pintype "passive"))
      (node (ref "C68") (pin "1") (pinfunction "1_1") (pintype "passive"))
      (node (ref "C69") (pin "2") (pinfunction "2_2") (pintype "passive"))
      (node (ref "C7") (pin "2") (pinfunction "2_2") (pintype "passive"))
      (node (ref "C70") (pin "1") (pinfunction "1_1") (pintype "passive"))
      (node (ref "C71") (pin "2") (pinfunction "2_2") (pintype "passive"))
      (node (ref "C8") (pin "2") (pinfunction "2_2") (pintype "passive"))
      (node (ref "C83") (pin "2") (pinfunction "2_2") (pintype "passive"))
      (node (ref "C84") (pin "2") (pinfunction "2_2") (pintype "passive"))
      (node (ref "C85") (pin "2") (pinfunction "2_2") (pintype "passive"))
      (node (ref "C86") (pin "2") (pinfunction "2_2") (pintype "passive"))
      (node (ref "C87") (pin "2") (pinfunction "2_2") (pintype "passive"))
      (node (ref "C88") (pin "2") (pinfunction "2_2") (pintype "passive"))
      (node (ref "C89") (pin "2") (pinfunction "2_2") (pintype "passive"))
      (node (ref "C9") (pin "1") (pinfunction "1_1") (pintype "passive"))
      (node (ref "C90") (pin "2") (pinfunction "2_2") (pintype "passive"))
      (node (ref "C91") (pin "2") (pinfunction "2_2") (pintype "passive"))
      (node (ref "C92") (pin "1") (pinfunction "1_1") (pintype "passive"))
      (node (ref "C93") (pin "1") (pinfunction "1_1") (pintype "passive"))
      (node (ref "C94") (pin "2") (pinfunction "2_2") (pintype "passive"))
      (node (ref "C95") (pin "1") (pinfunction "1_1") (pintype "passive"))
      (node (ref "C96") (pin "1") (pinfunction "1_1") (pintype "passive"))
      (node (ref "D2") (pin "1") (pinfunction "C_1") (pintype "passive"))
      (node (ref "D9") (pin "C") (pinfunction "C_C") (pintype "passive"))
      (node (ref "IC10") (pin "3") (pinfunction "IN+_3") (pintype "input"))
      (node (ref "JP1") (pin "2") (pinfunction "2_2") (pintype "passive"))
      (node (ref "JP2") (pin "2") (pinfunction "2_2") (pintype "passive"))
      (node (ref "JP3") (pin "2") (pinfunction "2_2") (pintype "passive"))
      (node (ref "JP4") (pin "1") (pinfunction "1_1") (pintype "passive"))
      (node (ref "R1") (pin "E") (pinfunction "3_E") (pintype "passive"))
      (node (ref "R16") (pin "1") (pinfunction "1_1") (pintype "passive"))
      (node (ref "R17") (pin "1") (pinfunction "1_1") (pintype "passive"))
      (node (ref "R18") (pin "2") (pinfunction "2_2") (pintype "passive"))
      (node (ref "R24") (pin "1") (pinfunction "1_1") (pintype "passive"))
      (node (ref "R31") (pin "1") (pinfunction "1_1") (pintype "passive"))
      (node (ref "R32") (pin "1") (pinfunction "1_1") (pintype "passive"))
      (node (ref "R39") (pin "1") (pinfunction "1_1") (pintype "passive"))
      (node (ref "R4") (pin "2") (pinfunction "2_2") (pintype "passive"))
      (node (ref "R5") (pin "2") (pinfunction "2_2") (pintype "passive"))
      (node (ref "R53") (pin "A") (pinfunction "1_A") (pintype "passive"))
      (node (ref "R9") (pin "A") (pinfunction "1_A") (pintype "passive"))
      (node (ref "S2") (pin "1") (pinfunction "1_1") (pintype "bidirectional"))
      (node (ref "S3") (pin "3") (pinfunction "3_3") (pintype "passive"))
      (node (ref "TP2") (pin "P$1") (pinfunction "P$1_P$1") (pintype "bidirectional"))
      (node (ref "X1") (pin "2") (pinfunction "2_2") (pintype "passive"))
      (node (ref "X5") (pin "2") (pinfunction "S_2") (pintype "passive"))
      (node (ref "X7") (pin "2") (pinfunction "S_2") (pintype "passive"))
    )
    (net (code "6") (name "Net-(C5-Pad1)") (class "Default")
      (node (ref "C5") (pin "1") (pinfunction "1_1") (pintype "passive"))
      (node (ref "D5") (pin "A") (pinfunction "A_A") (pintype "passive"))
      (node (ref "D6") (pin "C") (pinfunction "C_C") (pintype "passive"))
      (node (ref "R62") (pin "1") (pinfunction "1_1") (pintype "passive"))
      (node (ref "R64") (pin "2") (pinfunction "2_2") (pintype "passive"))
    )
    (net (code "7") (name "Net-(C6-Pad1)") (class "Default")
      (node (ref "C6") (pin "1") (pinfunction "1_1") (pintype "passive"))
      (node (ref "D7") (pin "A") (pinfunction "A_A") (pintype "passive"))
      (node (ref "D8") (pin "C") (pinfunction "C_C") (pintype "passive"))
      (node (ref "R63") (pin "1") (pinfunction "1_1") (pintype "passive"))
      (node (ref "R65") (pin "2") (pinfunction "2_2") (pintype "passive"))
    )
    (net (code "8") (name "Net-(C22-Pad1)") (class "Default")
      (node (ref "C22") (pin "1") (pinfunction "1_1") (pintype "passive"))
      (node (ref "S2") (pin "2") (pinfunction "2_2") (pintype "bidirectional"))
    )
    (net (code "9") (name "Net-(C71-Pad1)") (class "Default")
      (node (ref "C71") (pin "1") (pinfunction "1_1") (pintype "passive"))
      (node (ref "S2") (pin "3") (pinfunction "3_3") (pintype "bidirectional"))
    )
    (net (code "10") (name "Net-(C72-Pad1)") (class "Default")
      (node (ref "C72") (pin "1") (pinfunction "1_1") (pintype "passive"))
      (node (ref "S1") (pin "2") (pinfunction "2_2") (pintype "bidirectional"))
    )
    (net (code "11") (name "Net-(C73-Pad1)") (class "Default")
      (node (ref "C73") (pin "1") (pinfunction "1_1") (pintype "passive"))
      (node (ref "S1") (pin "3") (pinfunction "3_3") (pintype "bidirectional"))
    )
    (net (code "12") (name "Net-(C74-Pad1)") (class "Default")
      (node (ref "C74") (pin "1") (pinfunction "1_1") (pintype "passive"))
      (node (ref "S1") (pin "4") (pinfunction "4_4") (pintype "bidirectional"))
    )
    (net (code "13") (name "Net-(C75-Pad1)") (class "Default")
      (node (ref "C75") (pin "1") (pinfunction "1_1") (pintype "passive"))
      (node (ref "S1") (pin "5") (pinfunction "5_5") (pintype "bidirectional"))
    )
    (net (code "14") (name "Net-(C76-Pad1)") (class "Default")
      (node (ref "C76") (pin "1") (pinfunction "1_1") (pintype "passive"))
      (node (ref "S1") (pin "6") (pinfunction "6_6") (pintype "bidirectional"))
    )
    (net (code "15") (name "Net-(C77-Pad1)") (class "Default")
      (node (ref "C77") (pin "1") (pinfunction "1_1") (pintype "passive"))
      (node (ref "S1") (pin "7") (pinfunction "7_7") (pintype "bidirectional"))
    )
    (net (code "16") (name "Net-(C78-Pad1)") (class "Default")
      (node (ref "C78") (pin "1") (pinfunction "1_1") (pintype "passive"))
      (node (ref "S1") (pin "8") (pinfunction "8_8") (pintype "bidirectional"))
    )
    (net (code "17") (name "Net-(C79-Pad1)") (class "Default")
      (node (ref "C79") (pin "1") (pinfunction "1_1") (pintype "passive"))
      (node (ref "S1") (pin "9") (pinfunction "9_9") (pintype "bidirectional"))
    )
    (net (code "18") (name "Net-(C80-Pad1)") (class "Default")
      (node (ref "C80") (pin "1") (pinfunction "1_1") (pintype "passive"))
      (node (ref "S1") (pin "10") (pinfunction "10_10") (pintype "bidirectional"))
    )
    (net (code "19") (name "Net-(C81-Pad1)") (class "Default")
      (node (ref "C81") (pin "1") (pinfunction "1_1") (pintype "passive"))
      (node (ref "S1") (pin "11") (pinfunction "11_11") (pintype "bidirectional"))
    )
    (net (code "20") (name "Net-(C82-Pad1)") (class "Default")
      (node (ref "C82") (pin "1") (pinfunction "1_1") (pintype "passive"))
      (node (ref "S1") (pin "12") (pinfunction "12_12") (pintype "bidirectional"))
    )
    (net (code "21") (name "Net-(C83-Pad1)") (class "Default")
      (node (ref "C83") (pin "1") (pinfunction "1_1") (pintype "passive"))
      (node (ref "S2") (pin "4") (pinfunction "4_4") (pintype "bidirectional"))
    )
    (net (code "22") (name "Net-(C84-Pad1)") (class "Default")
      (node (ref "C84") (pin "1") (pinfunction "1_1") (pintype "passive"))
      (node (ref "S2") (pin "5") (pinfunction "5_5") (pintype "bidirectional"))
    )
    (net (code "23") (name "Net-(C85-Pad1)") (class "Default")
      (node (ref "C85") (pin "1") (pinfunction "1_1") (pintype "passive"))
      (node (ref "S2") (pin "6") (pinfunction "6_6") (pintype "bidirectional"))
    )
    (net (code "24") (name "Net-(C86-Pad1)") (class "Default")
      (node (ref "C86") (pin "1") (pinfunction "1_1") (pintype "passive"))
      (node (ref "S2") (pin "7") (pinfunction "7_7") (pintype "bidirectional"))
    )
    (net (code "25") (name "Net-(C87-Pad1)") (class "Default")
      (node (ref "C87") (pin "1") (pinfunction "1_1") (pintype "passive"))
      (node (ref "S2") (pin "8") (pinfunction "8_8") (pintype "bidirectional"))
    )
    (net (code "26") (name "Net-(C88-Pad1)") (class "Default")
      (node (ref "C88") (pin "1") (pinfunction "1_1") (pintype "passive"))
      (node (ref "S2") (pin "9") (pinfunction "9_9") (pintype "bidirectional"))
    )
    (net (code "27") (name "Net-(C89-Pad1)") (class "Default")
      (node (ref "C89") (pin "1") (pinfunction "1_1") (pintype "passive"))
      (node (ref "S2") (pin "10") (pinfunction "10_10") (pintype "bidirectional"))
    )
    (net (code "28") (name "Net-(C90-Pad1)") (class "Default")
      (node (ref "C90") (pin "1") (pinfunction "1_1") (pintype "passive"))
      (node (ref "S2") (pin "11") (pinfunction "11_11") (pintype "bidirectional"))
    )
    (net (code "29") (name "Net-(C91-Pad1)") (class "Default")
      (node (ref "C91") (pin "1") (pinfunction "1_1") (pintype "passive"))
      (node (ref "S2") (pin "12") (pinfunction "12_12") (pintype "bidirectional"))
    )
    (net (code "30") (name "Net-(D1-PadA)") (class "Default")
      (node (ref "D1") (pin "A") (pinfunction "A_A") (pintype "passive"))
      (node (ref "R2") (pin "1") (pinfunction "1_1") (pintype "passive"))
      (node (ref "R3") (pin "2") (pinfunction "2_2") (pintype "passive"))
    )
    (net (code "31") (name "Net-(D1-PadC)") (class "Default")
      (node (ref "D1") (pin "C") (pinfunction "C_C") (pintype "passive"))
      (node (ref "D4") (pin "A") (pinfunction "A_A") (pintype "passive"))
      (node (ref "R2") (pin "2") (pinfunction "2_2") (pintype "passive"))
      (node (ref "S3") (pin "2") (pinfunction "2_2") (pintype "passive"))
    )
    (net (code "32") (name "Net-(D2-A)") (class "Default")
      (node (ref "C1") (pin "2") (pinfunction "2_2") (pintype "passive"))
      (node (ref "D2") (pin "2") (pinfunction "A_2") (pintype "passive"))
      (node (ref "R53") (pin "E") (pinfunction "3_E") (pintype "passive"))
      (node (ref "R7") (pin "2") (pinfunction "2_2") (pintype "passive"))
      (node (ref "R9") (pin "E") (pinfunction "3_E") (pintype "passive"))
    )
    (net (code "33") (name "Net-(D4-PadC)") (class "Default")
      (node (ref "D4") (pin "C") (pinfunction "C_C") (pintype "passive"))
      (node (ref "R60") (pin "2") (pinfunction "2_2") (pintype "passive"))
    )
    (net (code "34") (name "Net-(D9-PadA)") (class "Default")
      (node (ref "D9") (pin "A") (pinfunction "A_A") (pintype "passive"))
      (node (ref "R66") (pin "1") (pinfunction "1_1") (pintype "passive"))
    )
    (net (code "35") (name "Net-(D12-1)") (class "Default")
      (node (ref "D12") (pin "A") (pinfunction "1_A") (pintype "passive"))
      (node (ref "R58") (pin "1") (pinfunction "1_1") (pintype "passive"))
      (node (ref "X4") (pin "2") (pinfunction "2_2") (pintype "passive"))
      (node (ref "X4") (pin "3") (pinfunction "2_3") (pintype "passive"))
      (node (ref "X4") (pin "4") (pinfunction "2_4") (pintype "passive"))
      (node (ref "X4") (pin "5") (pinfunction "2_5") (pintype "passive"))
    )
    (net (code "36") (name "Net-(D12-2)") (class "Default")
      (node (ref "C6") (pin "2") (pinfunction "2_2") (pintype "passive"))
      (node (ref "D12") (pin "C") (pinfunction "2_C") (pintype "passive"))
      (node (ref "R65") (pin "1") (pinfunction "1_1") (pintype "passive"))
      (node (ref "X4") (pin "1") (pinfunction "1_1") (pintype "passive"))
    )
    (net (code "37") (name "Net-(D13-1)") (class "Default")
      (node (ref "D13") (pin "A") (pinfunction "1_A") (pintype "passive"))
      (node (ref "R6") (pin "1") (pinfunction "1_1") (pintype "passive"))
      (node (ref "X2") (pin "2") (pinfunction "2_2") (pintype "passive"))
      (node (ref "X2") (pin "3") (pinfunction "2_3") (pintype "passive"))
      (node (ref "X2") (pin "4") (pinfunction "2_4") (pintype "passive"))
      (node (ref "X2") (pin "5") (pinfunction "2_5") (pintype "passive"))
    )
    (net (code "38") (name "Net-(D13-2)") (class "Default")
      (node (ref "C5") (pin "2") (pinfunction "2_2") (pintype "passive"))
      (node (ref "D13") (pin "C") (pinfunction "2_C") (pintype "passive"))
      (node (ref "R64") (pin "1") (pinfunction "1_1") (pintype "passive"))
      (node (ref "X2") (pin "1") (pinfunction "1_1") (pintype "passive"))
    )
    (net (code "39") (name "Net-(D14-PadA)") (class "Default")
      (node (ref "D14") (pin "A") (pinfunction "A_A") (pintype "passive"))
      (node (ref "R18") (pin "1") (pinfunction "1_1") (pintype "passive"))
    )
    (net (code "40") (name "Net-(IC1-IN+)") (class "Default")
      (node (ref "IC1") (pin "3") (pinfunction "IN+_3") (pintype "input"))
      (node (ref "R20") (pin "1") (pinfunction "1_1") (pintype "passive"))
      (node (ref "R24") (pin "2") (pinfunction "2_2") (pintype "passive"))
    )
    (net (code "41") (name "Net-(IC1-IN-)") (class "Default")
      (node (ref "IC1") (pin "2") (pinfunction "IN-_2") (pintype "input"))
      (node (ref "R19") (pin "1") (pinfunction "1_1") (pintype "passive"))
      (node (ref "R23") (pin "2") (pinfunction "2_2") (pintype "passive"))
    )
    (net (code "42") (name "Net-(IC1-OUT)") (class "Default")
      (node (ref "IC1") (pin "6") (pinfunction "OUT_6") (pintype "output"))
      (node (ref "R23") (pin "1") (pinfunction "1_1") (pintype "passive"))
      (node (ref "R25") (pin "2") (pinfunction "2_2") (pintype "passive"))
      (node (ref "R40") (pin "2") (pinfunction "2_2") (pintype "passive"))
    )
    (net (code "43") (name "Net-(IC2-COMP)") (class "Default")
      (node (ref "C13") (pin "1") (pinfunction "1_1") (pintype "passive"))
      (node (ref "IC2") (pin "8") (pinfunction "COMP_8") (pintype "passive"))
    )
    (net (code "44") (name "Net-(IC2-IN+)") (class "Default")
      (node (ref "C10") (pin "1") (pinfunction "1_1") (pintype "passive"))
      (node (ref "IC2") (pin "3") (pinfunction "IN+_3") (pintype "input"))
      (node (ref "JP4") (pin "2") (pinfunction "2_2") (pintype "passive"))
      (node (ref "R14") (pin "2") (pinfunction "2_2") (pintype "passive"))
      (node (ref "R16") (pin "2") (pinfunction "2_2") (pintype "passive"))
      (node (ref "R70") (pin "2") (pinfunction "SA_2") (pintype "passive"))
      (node (ref "X6") (pin "2") (pinfunction "S_2") (pintype "passive"))
    )
    (net (code "45") (name "Net-(IC2-IN-)") (class "Default")
      (node (ref "C14") (pin "1") (pinfunction "1_1") (pintype "passive"))
      (node (ref "IC2") (pin "2") (pinfunction "IN-_2") (pintype "input"))
      (node (ref "R13") (pin "2") (pinfunction "2_2") (pintype "passive"))
      (node (ref "R21") (pin "2") (pinfunction "2_2") (pintype "passive"))
    )
    (net (code "46") (name "Net-(IC2-OUT)") (class "Default")
      (node (ref "C13") (pin "2") (pinfunction "2_2") (pintype "passive"))
      (node (ref "C14") (pin "2") (pinfunction "2_2") (pintype "passive"))
      (node (ref "IC2") (pin "6") (pinfunction "OUT_6") (pintype "output"))
      (node (ref "R19") (pin "2") (pinfunction "2_2") (pintype "passive"))
      (node (ref "R21") (pin "1") (pinfunction "1_1") (pintype "passive"))
    )
    (net (code "47") (name "Net-(IC3-IN)") (class "Default")
      (node (ref "IC3") (pin "3") (pinfunction "IN_3") (pintype "input"))
      (node (ref "R57") (pin "1") (pinfunction "1_1") (pintype "passive"))
    )
    (net (code "48") (name "Net-(IC3-OUT)") (class "Default")
      (node (ref "IC3") (pin "6") (pinfunction "OUT_6") (pintype "output"))
      (node (ref "R63") (pin "2") (pinfunction "2_2") (pintype "passive"))
    )
    (net (code "49") (name "Net-(IC4-COMP)") (class "Default")
      (node (ref "C12") (pin "1") (pinfunction "1_1") (pintype "passive"))
      (node (ref "IC4") (pin "8") (pinfunction "COMP_8") (pintype "passive"))
    )
    (net (code "50") (name "Net-(IC4-IN+)") (class "Default")
      (node (ref "C11") (pin "1") (pinfunction "1_1") (pintype "passive"))
      (node (ref "IC4") (pin "3") (pinfunction "IN+_3") (pintype "input"))
      (node (ref "JP3") (pin "1") (pinfunction "1_1") (pintype "passive"))
      (node (ref "R15") (pin "1") (pinfunction "1_1") (pintype "passive"))
      (node (ref "R17") (pin "2") (pinfunction "2_2") (pintype "passive"))
      (node (ref "R70") (pin "3") (pinfunction "SB_3") (pintype "passive"))
      (node (ref "X6") (pin "3") (pinfunction "S_3") (pintype "passive"))
    )
    (net (code "51") (name "Net-(IC4-IN-)") (class "Default")
      (node (ref "C15") (pin "1") (pinfunction "1_1") (pintype "passive"))
      (node (ref "IC4") (pin "2") (pinfunction "IN-_2") (pintype "input"))
      (node (ref "R13") (pin "1") (pinfunction "1_1") (pintype "passive"))
      (node (ref "R22") (pin "2") (pinfunction "2_2") (pintype "passive"))
    )
    (net (code "52") (name "Net-(IC4-OUT)") (class "Default")
      (node (ref "C12") (pin "2") (pinfunction "2_2") (pintype "passive"))
      (node (ref "C15") (pin "2") (pinfunction "2_2") (pintype "passive"))
      (node (ref "IC4") (pin "6") (pinfunction "OUT_6") (pintype "output"))
      (node (ref "R20") (pin "2") (pinfunction "2_2") (pintype "passive"))
      (node (ref "R22") (pin "1") (pinfunction "1_1") (pintype "passive"))
    )
    (net (code "53") (name "Net-(IC5-IN+)") (class "Default")
      (node (ref "IC5") (pin "3") (pinfunction "IN+_3") (pintype "input"))
      (node (ref "R42") (pin "1") (pinfunction "1_1") (pintype "passive"))
    )
    (net (code "54") (name "Net-(IC5-IN-)") (class "Default")
      (node (ref "IC5") (pin "2") (pinfunction "IN-_2") (pintype "input"))
      (node (ref "R43") (pin "2") (pinfunction "2_2") (pintype "passive"))
    )
    (net (code "55") (name "Net-(IC5-OUT)") (class "Default")
      (node (ref "C72") (pin "2") (pinfunction "2_2") (pintype "passive"))
      (node (ref "C73") (pin "2") (pinfunction "2_2") (pintype "passive"))
      (node (ref "C74") (pin "2") (pinfunction "2_2") (pintype "passive"))
      (node (ref "C75") (pin "2") (pinfunction "2_2") (pintype "passive"))
      (node (ref "C76") (pin "2") (pinfunction "2_2") (pintype "passive"))
      (node (ref "C77") (pin "2") (pinfunction "2_2") (pintype "passive"))
      (node (ref "C78") (pin "2") (pinfunction "2_2") (pintype "passive"))
      (node (ref "C79") (pin "2") (pinfunction "2_2") (pintype "passive"))
      (node (ref "C80") (pin "2") (pinfunction "2_2") (pintype "passive"))
      (node (ref "C81") (pin "2") (pinfunction "2_2") (pintype "passive"))
      (node (ref "C82") (pin "2") (pinfunction "2_2") (pintype "passive"))
      (node (ref "IC5") (pin "6") (pinfunction "OUT_6") (pintype "output"))
      (node (ref "R45") (pin "2") (pinfunction "2_2") (pintype "passive"))
      (node (ref "S1") (pin "1") (pinfunction "1_1") (pintype "bidirectional"))
    )
    (net (code "56") (name "Net-(IC6-IN+)") (class "Default")
      (node (ref "IC6") (pin "3") (pinfunction "IN+_3") (pintype "input"))
      (node (ref "R25") (pin "1") (pinfunction "1_1") (pintype "passive"))
    )
    (net (code "57") (name "Net-(IC6-IN-)") (class "Default")
      (node (ref "IC6") (pin "2") (pinfunction "IN-_2") (pintype "input"))
      (node (ref "IC6") (pin "6") (pinfunction "OUT_6") (pintype "output"))
      (node (ref "R27") (pin "2") (pinfunction "2_2") (pintype "passive"))
    )
    (net (code "58") (name "Net-(IC7-COMP)") (class "Default")
      (node (ref "C19") (pin "1") (pinfunction "1_1") (pintype "passive"))
      (node (ref "IC7") (pin "8") (pinfunction "COMP_8") (pintype "passive"))
    )
    (net (code "59") (name "Net-(IC7-IN+)") (class "Default")
      (node (ref "C16") (pin "1") (pinfunction "1_1") (pintype "passive"))
      (node (ref "IC7") (pin "3") (pinfunction "IN+_3") (pintype "input"))
      (node (ref "R29") (pin "2") (pinfunction "2_2") (pintype "passive"))
      (node (ref "R31") (pin "2") (pinfunction "2_2") (pintype "passive"))
    )
    (net (code "60") (name "Net-(IC7-IN-)") (class "Default")
      (node (ref "C20") (pin "1") (pinfunction "1_1") (pintype "passive"))
      (node (ref "IC7") (pin "2") (pinfunction "IN-_2") (pintype "input"))
      (node (ref "R28") (pin "2") (pinfunction "2_2") (pintype "passive"))
      (node (ref "R36") (pin "2") (pinfunction "2_2") (pintype "passive"))
    )
    (net (code "61") (name "Net-(IC7-OUT)") (class "Default")
      (node (ref "C19") (pin "2") (pinfunction "2_2") (pintype "passive"))
      (node (ref "C20") (pin "2") (pinfunction "2_2") (pintype "passive"))
      (node (ref "IC7") (pin "6") (pinfunction "OUT_6") (pintype "output"))
      (node (ref "R34") (pin "2") (pinfunction "2_2") (pintype "passive"))
      (node (ref "R36") (pin "1") (pinfunction "1_1") (pintype "passive"))
    )
    (net (code "62") (name "Net-(IC8-COMP)") (class "Default")
      (node (ref "C18") (pin "1") (pinfunction "1_1") (pintype "passive"))
      (node (ref "IC8") (pin "8") (pinfunction "COMP_8") (pintype "passive"))
    )
    (net (code "63") (name "Net-(IC8-IN+)") (class "Default")
      (node (ref "C17") (pin "1") (pinfunction "1_1") (pintype "passive"))
      (node (ref "IC8") (pin "3") (pinfunction "IN+_3") (pintype "input"))
      (node (ref "R30") (pin "1") (pinfunction "1_1") (pintype "passive"))
      (node (ref "R32") (pin "2") (pinfunction "2_2") (pintype "passive"))
    )
    (net (code "64") (name "Net-(IC8-IN-)") (class "Default")
      (node (ref "C21") (pin "1") (pinfunction "1_1") (pintype "passive"))
      (node (ref "IC8") (pin "2") (pinfunction "IN-_2") (pintype "input"))
      (node (ref "R28") (pin "1") (pinfunction "1_1") (pintype "passive"))
      (node (ref "R37") (pin "2") (pinfunction "2_2") (pintype "passive"))
    )
    (net (code "65") (name "Net-(IC8-OUT)") (class "Default")
      (node (ref "C18") (pin "2") (pinfunction "2_2") (pintype "passive"))
      (node (ref "C21") (pin "2") (pinfunction "2_2") (pintype "passive"))
      (node (ref "IC8") (pin "6") (pinfunction "OUT_6") (pintype "output"))
      (node (ref "R35") (pin "2") (pinfunction "2_2") (pintype "passive"))
      (node (ref "R37") (pin "1") (pinfunction "1_1") (pintype "passive"))
    )
    (net (code "66") (name "Net-(IC9-IN+)") (class "Default")
      (node (ref "IC9") (pin "3") (pinfunction "IN+_3") (pintype "input"))
      (node (ref "R35") (pin "1") (pinfunction "1_1") (pintype "passive"))
      (node (ref "R39") (pin "2") (pinfunction "2_2") (pintype "passive"))
    )
    (net (code "67") (name "Net-(IC9-IN-)") (class "Default")
      (node (ref "IC9") (pin "2") (pinfunction "IN-_2") (pintype "input"))
      (node (ref "R34") (pin "1") (pinfunction "1_1") (pintype "passive"))
      (node (ref "R38") (pin "2") (pinfunction "2_2") (pintype "passive"))
    )
    (net (code "68") (name "Net-(IC9-OUT)") (class "Default")
      (node (ref "IC9") (pin "6") (pinfunction "OUT_6") (pintype "output"))
      (node (ref "R33") (pin "2") (pinfunction "2_2") (pintype "passive"))
      (node (ref "R38") (pin "1") (pinfunction "1_1") (pintype "passive"))
      (node (ref "TP1") (pin "P$1") (pinfunction "P$1_P$1") (pintype "bidirectional"))
    )
    (net (code "69") (name "Net-(IC10-IN-)") (class "Default")
      (node (ref "IC10") (pin "2") (pinfunction "IN-_2") (pintype "input"))
      (node (ref "R33") (pin "1") (pinfunction "1_1") (pintype "passive"))
      (node (ref "R40") (pin "1") (pinfunction "1_1") (pintype "passive"))
      (node (ref "R41") (pin "2") (pinfunction "2_2") (pintype "passive"))
    )
    (net (code "70") (name "Net-(IC10-OUT)") (class "Default")
      (node (ref "IC10") (pin "6") (pinfunction "OUT_6") (pintype "output"))
      (node (ref "R0") (pin "2") (pinfunction "2_2") (pintype "passive"))
      (node (ref "R0") (pin "3") (pinfunction "3_3") (pintype "passive"))
      (node (ref "R42") (pin "2") (pinfunction "2_2") (pintype "passive"))
    )
    (net (code "71") (name "Net-(IC11-IN+)") (class "Default")
      (node (ref "IC11") (pin "3") (pinfunction "IN+_3") (pintype "input"))
      (node (ref "R45") (pin "1") (pinfunction "1_1") (pintype "passive"))
      (node (ref "R46") (pin "1") (pinfunction "1_1") (pintype "passive"))
    )
    (net (code "72") (name "Net-(IC11-IN-)") (class "Default")
      (node (ref "IC11") (pin "2") (pinfunction "IN-_2") (pintype "input"))
      (node (ref "R47") (pin "2") (pinfunction "2_2") (pintype "passive"))
    )
    (net (code "73") (name "Net-(IC11-OUT)") (class "Default")
      (node (ref "IC11") (pin "6") (pinfunction "OUT_6") (pintype "output"))
      (node (ref "R48") (pin "1") (pinfunction "1_1") (pintype "passive"))
      (node (ref "R50") (pin "A") (pinfunction "1_A") (pintype "passive"))
      (node (ref "R50") (pin "S") (pinfunction "2_S") (pintype "passive"))
    )
    (net (code "74") (name "Net-(IC12-IN+)") (class "Default")
      (node (ref "C23") (pin "1") (pinfunction "1_1") (pintype "passive"))
      (node (ref "IC12") (pin "3") (pinfunction "IN+_3") (pintype "input"))
      (node (ref "R52") (pin "1") (pinfunction "1_1") (pintype "passive"))
    )
    (net (code "75") (name "Net-(IC12-IN-)") (class "Default")
      (node (ref "IC12") (pin "2") (pinfunction "IN-_2") (pintype "input"))
      (node (ref "IC12") (pin "6") (pinfunction "OUT_6") (pintype "output"))
      (node (ref "S3") (pin "1") (pinfunction "1_1") (pintype "passive"))
    )
    (net (code "76") (name "Net-(IC13-IN+)") (class "Default")
      (node (ref "IC13") (pin "3") (pinfunction "IN+_3") (pintype "input"))
      (node (ref "R4") (pin "1") (pinfunction "1_1") (pintype "passive"))
      (node (ref "R5") (pin "1") (pinfunction "1_1") (pintype "passive"))
      (node (ref "R6") (pin "2") (pinfunction "2_2") (pintype "passive"))
    )
    (net (code "77") (name "Net-(IC13-IN-)") (class "Default")
      (node (ref "IC13") (pin "2") (pinfunction "IN-_2") (pintype "input"))
      (node (ref "R3") (pin "1") (pinfunction "1_1") (pintype "passive"))
      (node (ref "R55") (pin "1") (pinfunction "1_1") (pintype "passive"))
      (node (ref "R8") (pin "2") (pinfunction "2_2") (pintype "passive"))
    )
    (net (code "78") (name "Net-(IC13-OUT)") (class "Default")
      (node (ref "IC13") (pin "6") (pinfunction "OUT_6") (pintype "output"))
      (node (ref "R61") (pin "2") (pinfunction "2_2") (pintype "passive"))
      (node (ref "R8") (pin "1") (pinfunction "1_1") (pintype "passive"))
    )
    (net (code "79") (name "Net-(IC14-IN+)") (class "Default")
      (node (ref "C2") (pin "2") (pinfunction "2_2") (pintype "passive"))
      (node (ref "IC14") (pin "3") (pinfunction "IN+_3") (pintype "input"))
      (node (ref "R9") (pin "S") (pinfunction "2_S") (pintype "passive"))
    )
    (net (code "80") (name "Net-(IC15-IN+)") (class "Default")
      (node (ref "C4") (pin "2") (pinfunction "2_2") (pintype "passive"))
      (node (ref "IC15") (pin "3") (pinfunction "IN+_3") (pintype "input"))
      (node (ref "R53") (pin "S") (pinfunction "2_S") (pintype "passive"))
    )
    (net (code "81") (name "Net-(IC16-IN+)") (class "Default")
      (node (ref "IC16") (pin "3") (pinfunction "IN+_3") (pintype "input"))
      (node (ref "R58") (pin "2") (pinfunction "2_2") (pintype "passive"))
      (node (ref "R60") (pin "1") (pinfunction "1_1") (pintype "passive"))
    )
    (net (code "82") (name "Net-(IC16-IN-)") (class "Default")
      (node (ref "IC16") (pin "2") (pinfunction "IN-_2") (pintype "input"))
      (node (ref "R56") (pin "1") (pinfunction "1_1") (pintype "passive"))
      (node (ref "R59") (pin "2") (pinfunction "2_2") (pintype "passive"))
    )
    (net (code "83") (name "Net-(IC16-OUT)") (class "Default")
      (node (ref "IC16") (pin "6") (pinfunction "OUT_6") (pintype "output"))
      (node (ref "R57") (pin "2") (pinfunction "2_2") (pintype "passive"))
      (node (ref "R59") (pin "1") (pinfunction "1_1") (pintype "passive"))
    )
    (net (code "84") (name "Net-(IC17-IN)") (class "Default")
      (node (ref "IC17") (pin "3") (pinfunction "IN_3") (pintype "input"))
      (node (ref "R61") (pin "1") (pinfunction "1_1") (pintype "passive"))
    )
    (net (code "85") (name "Net-(IC17-OUT)") (class "Default")
      (node (ref "IC17") (pin "6") (pinfunction "OUT_6") (pintype "output"))
      (node (ref "R62") (pin "2") (pinfunction "2_2") (pintype "passive"))
    )
    (net (code "86") (name "Net-(JP1-Pad1)") (class "Default")
      (node (ref "JP1") (pin "1") (pinfunction "1_1") (pintype "passive"))
      (node (ref "R10") (pin "1") (pinfunction "1_1") (pintype "passive"))
      (node (ref "R55") (pin "2") (pinfunction "2_2") (pintype "passive"))
    )
    (net (code "87") (name "Net-(JP2-Pad1)") (class "Default")
      (node (ref "JP2") (pin "1") (pinfunction "1_1") (pintype "passive"))
      (node (ref "R54") (pin "1") (pinfunction "1_1") (pintype "passive"))
      (node (ref "R56") (pin "2") (pinfunction "2_2") (pintype "passive"))
    )
    (net (code "88") (name "Net-(R0-Pad1)") (class "Default")
      (node (ref "R0") (pin "1") (pinfunction "1_1") (pintype "passive"))
      (node (ref "R41") (pin "1") (pinfunction "1_1") (pintype "passive"))
    )
    (net (code "89") (name "Net-(R1-1)") (class "Default")
      (node (ref "R1") (pin "A") (pinfunction "1_A") (pintype "passive"))
      (node (ref "R1") (pin "S") (pinfunction "2_S") (pintype "passive"))
      (node (ref "R44") (pin "1") (pinfunction "1_1") (pintype "passive"))
    )
    (net (code "90") (name "Net-(R27-Pad1)") (class "Default")
      (node (ref "R27") (pin "1") (pinfunction "1_1") (pintype "passive"))
      (node (ref "X1") (pin "1") (pinfunction "1_1") (pintype "passive"))
    )
    (net (code "91") (name "Net-(R29-Pad1)") (class "Default")
      (node (ref "R29") (pin "1") (pinfunction "1_1") (pintype "passive"))
      (node (ref "X3") (pin "1") (pinfunction "1_1") (pintype "passive"))
    )
    (net (code "92") (name "Net-(R30-Pad2)") (class "Default")
      (node (ref "R30") (pin "2") (pinfunction "2_2") (pintype "passive"))
      (node (ref "X3") (pin "2") (pinfunction "2_2") (pintype "passive"))
    )
    (net (code "93") (name "Net-(R43-Pad1)") (class "Default")
      (node (ref "R43") (pin "1") (pinfunction "1_1") (pintype "passive"))
      (node (ref "R44") (pin "2") (pinfunction "2_2") (pintype "passive"))
      (node (ref "S1") (pin "13") (pinfunction "13_13") (pintype "bidirectional"))
    )
    (net (code "94") (name "Net-(R47-Pad1)") (class "Default")
      (node (ref "R47") (pin "1") (pinfunction "1_1") (pintype "passive"))
      (node (ref "R48") (pin "2") (pinfunction "2_2") (pintype "passive"))
      (node (ref "R49") (pin "2") (pinfunction "2_2") (pintype "passive"))
    )
    (net (code "95") (name "Net-(R50-3)") (class "Default")
      (node (ref "R50") (pin "E") (pinfunction "3_E") (pintype "passive"))
      (node (ref "R52") (pin "2") (pinfunction "2_2") (pintype "passive"))
    )
    (net (code "96") (name "Net-(R51-1)") (class "Default")
      (node (ref "R49") (pin "1") (pinfunction "1_1") (pintype "passive"))
      (node (ref "R51") (pin "A") (pinfunction "1_A") (pintype "passive"))
      (node (ref "R51") (pin "S") (pinfunction "2_S") (pintype "passive"))
    )
    (net (code "97") (name "Net-(R51-3)") (class "Default")
      (node (ref "R51") (pin "E") (pinfunction "3_E") (pintype "passive"))
      (node (ref "S2") (pin "13") (pinfunction "13_13") (pintype "bidirectional"))
    )
    (net (code "98") (name "Net-(R70-A)") (class "Default")
      (node (ref "R14") (pin "1") (pinfunction "1_1") (pintype "passive"))
      (node (ref "R70") (pin "1") (pinfunction "A_1") (pintype "passive"))
    )
    (net (code "99") (name "Net-(R70-B)") (class "Default")
      (node (ref "R15") (pin "2") (pinfunction "2_2") (pintype "passive"))
      (node (ref "R70") (pin "4") (pinfunction "B_4") (pintype "passive"))
    )
    (net (code "100") (name "unconnected-(IC2-OFF-Pad1)") (class "Default")
      (node (ref "IC2") (pin "1") (pinfunction "OFF_1") (pintype "passive"))
    )
    (net (code "101") (name "unconnected-(IC2-OFF-Pad5)") (class "Default")
      (node (ref "IC2") (pin "5") (pinfunction "OFF_5") (pintype "passive"))
    )
    (net (code "102") (name "unconnected-(IC3-BW-Pad1)") (class "Default")
      (node (ref "IC3") (pin "1") (pinfunction "BW_1") (pintype "passive"))
    )
    (net (code "103") (name "unconnected-(IC4-OFF-Pad1)") (class "Default")
      (node (ref "IC4") (pin "1") (pinfunction "OFF_1") (pintype "passive"))
    )
    (net (code "104") (name "unconnected-(IC4-OFF-Pad5)") (class "Default")
      (node (ref "IC4") (pin "5") (pinfunction "OFF_5") (pintype "passive"))
    )
    (net (code "105") (name "unconnected-(IC7-OFF-Pad1)") (class "Default")
      (node (ref "IC7") (pin "1") (pinfunction "OFF_1") (pintype "passive"))
    )
    (net (code "106") (name "unconnected-(IC7-OFF-Pad5)") (class "Default")
      (node (ref "IC7") (pin "5") (pinfunction "OFF_5") (pintype "passive"))
    )
    (net (code "107") (name "unconnected-(IC8-OFF-Pad1)") (class "Default")
      (node (ref "IC8") (pin "1") (pinfunction "OFF_1") (pintype "passive"))
    )
    (net (code "108") (name "unconnected-(IC8-OFF-Pad5)") (class "Default")
      (node (ref "IC8") (pin "5") (pinfunction "OFF_5") (pintype "passive"))
    )
    (net (code "109") (name "unconnected-(IC17-BW-Pad1)") (class "Default")
      (node (ref "IC17") (pin "1") (pinfunction "BW_1") (pintype "passive"))
    )
  )
)
